# SCH__Atlas_2026-06-21.net
KiCad netlist of a schematic drawn in EasyEDA
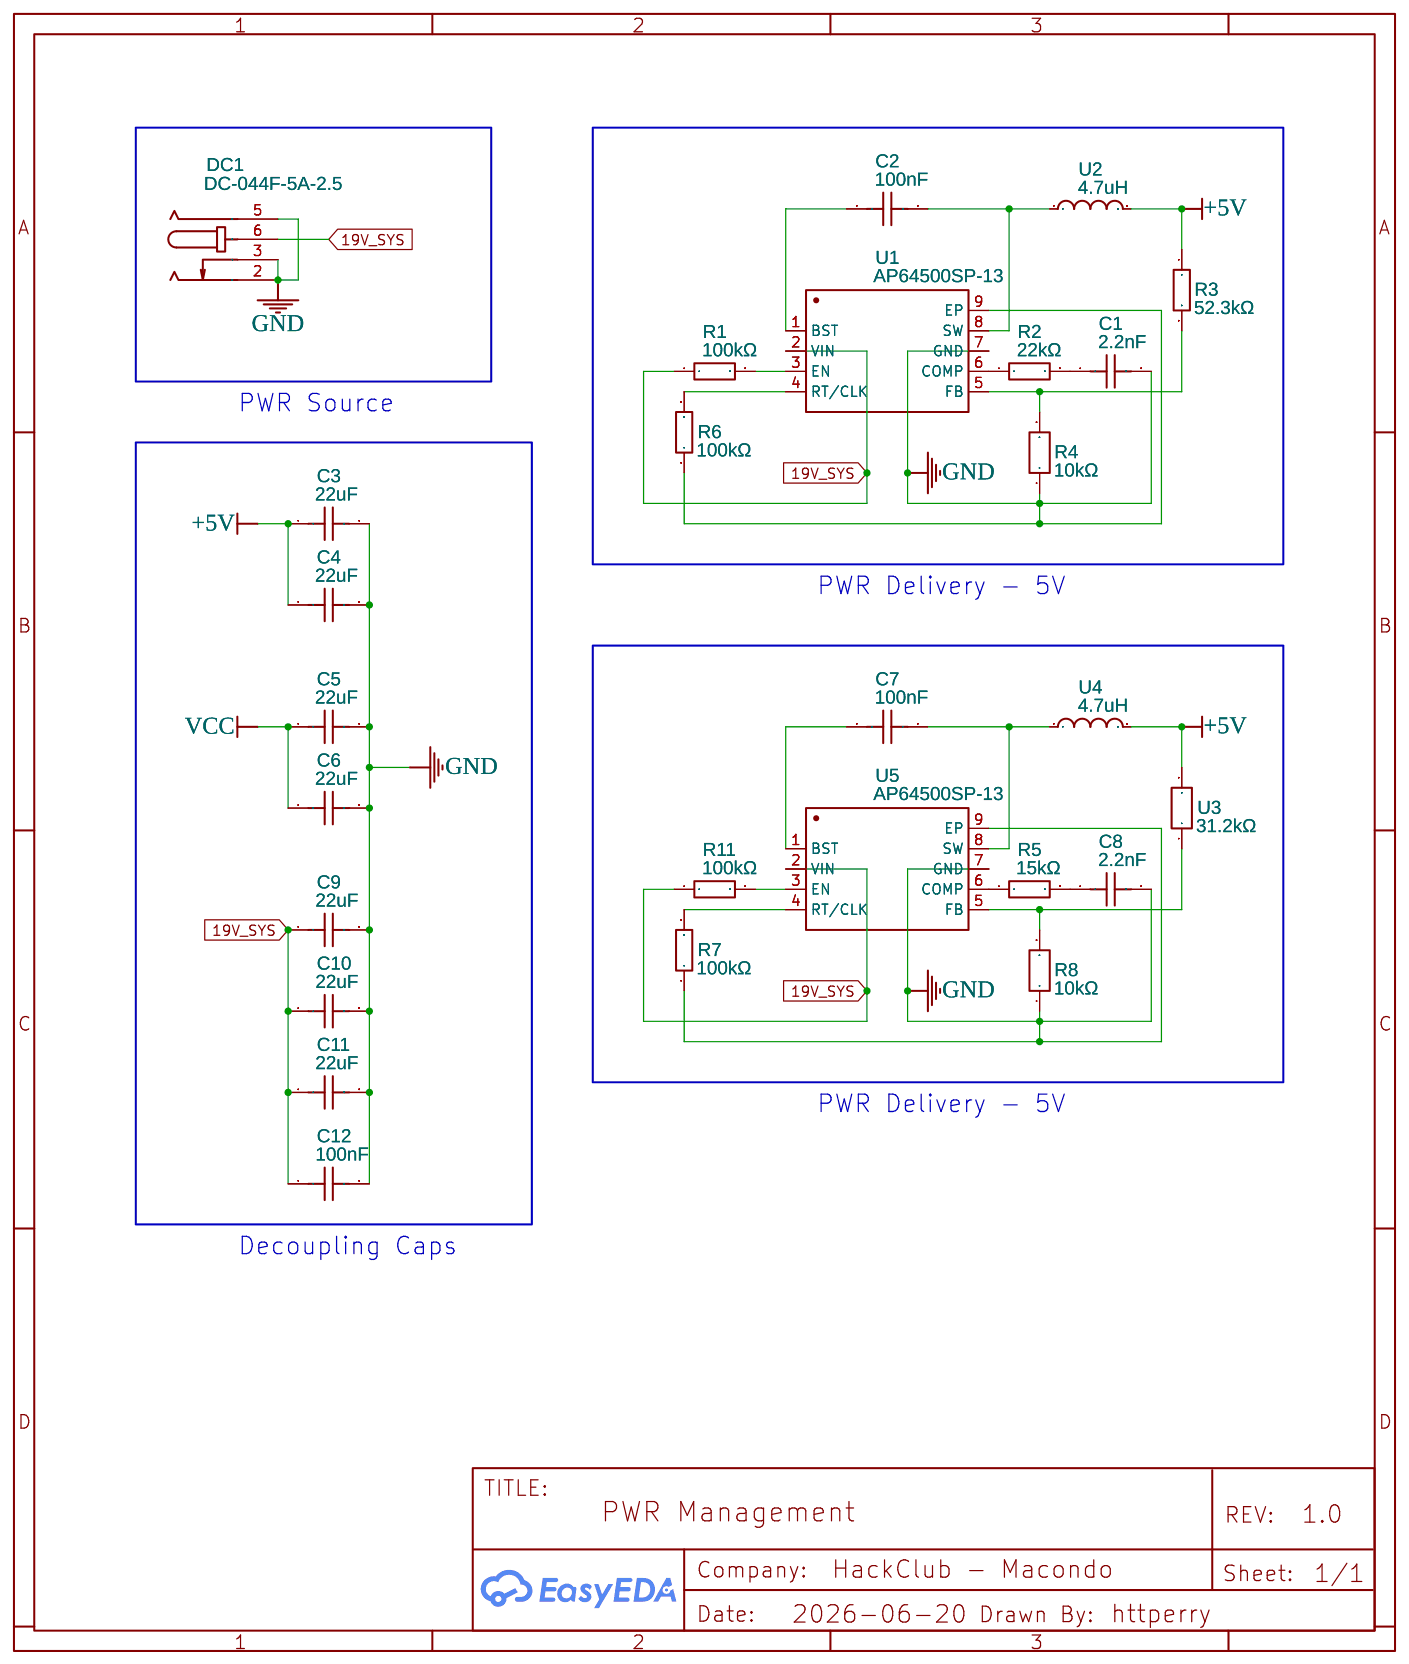
[diagram p0: PWR_Management]
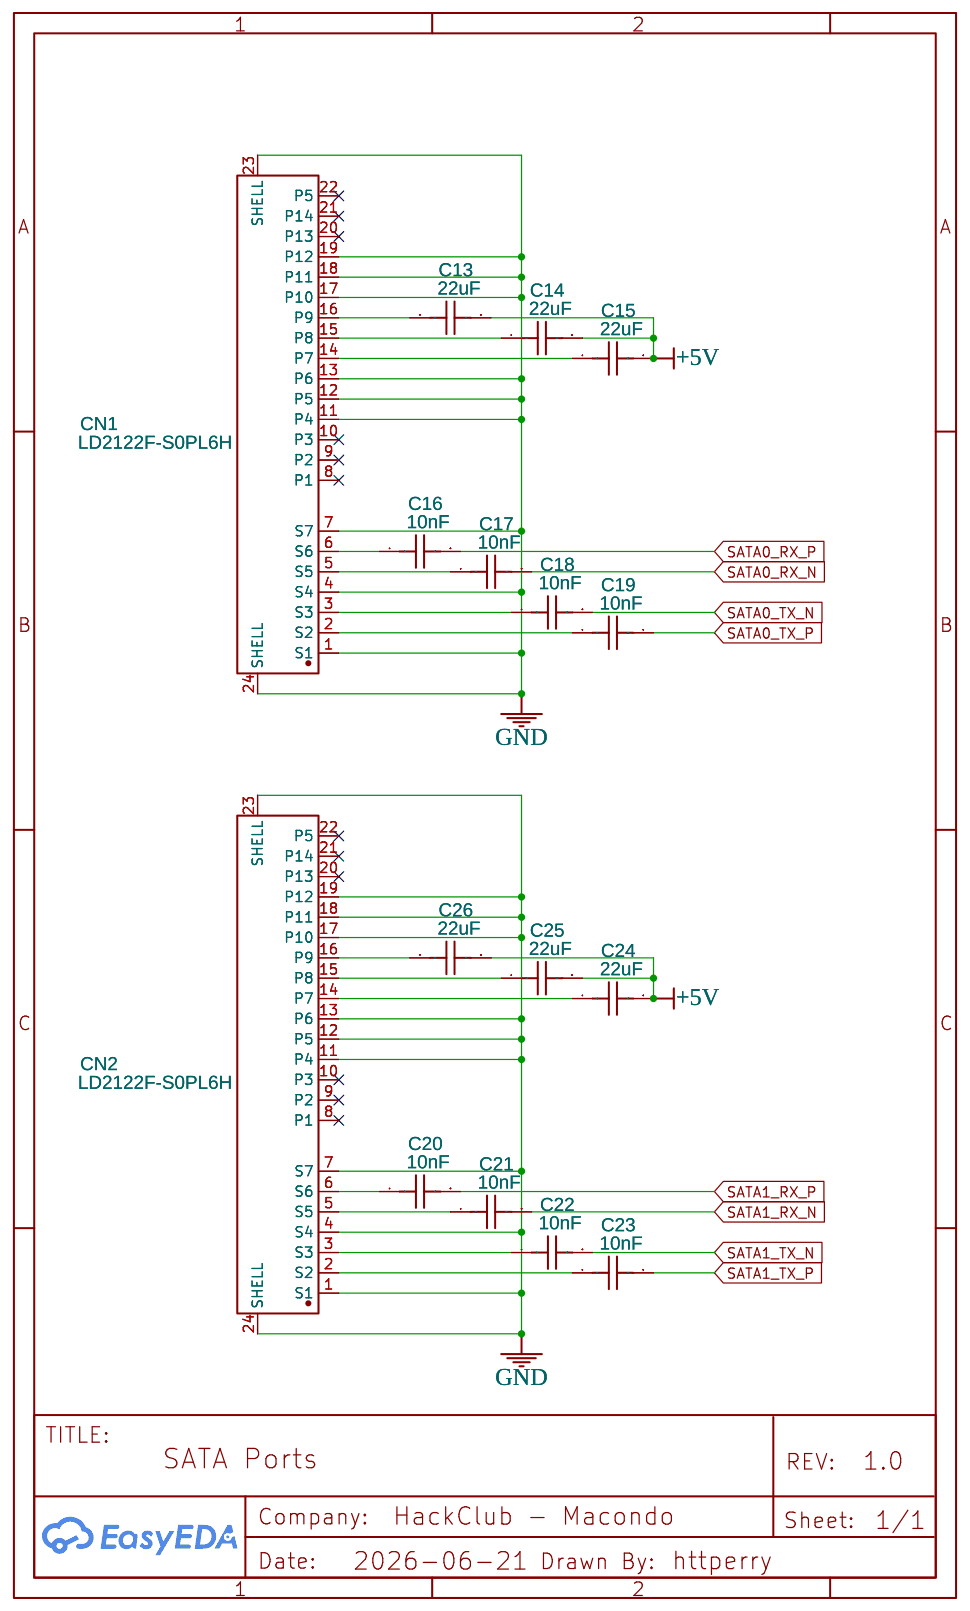
[diagram p1: SATA_Ports]
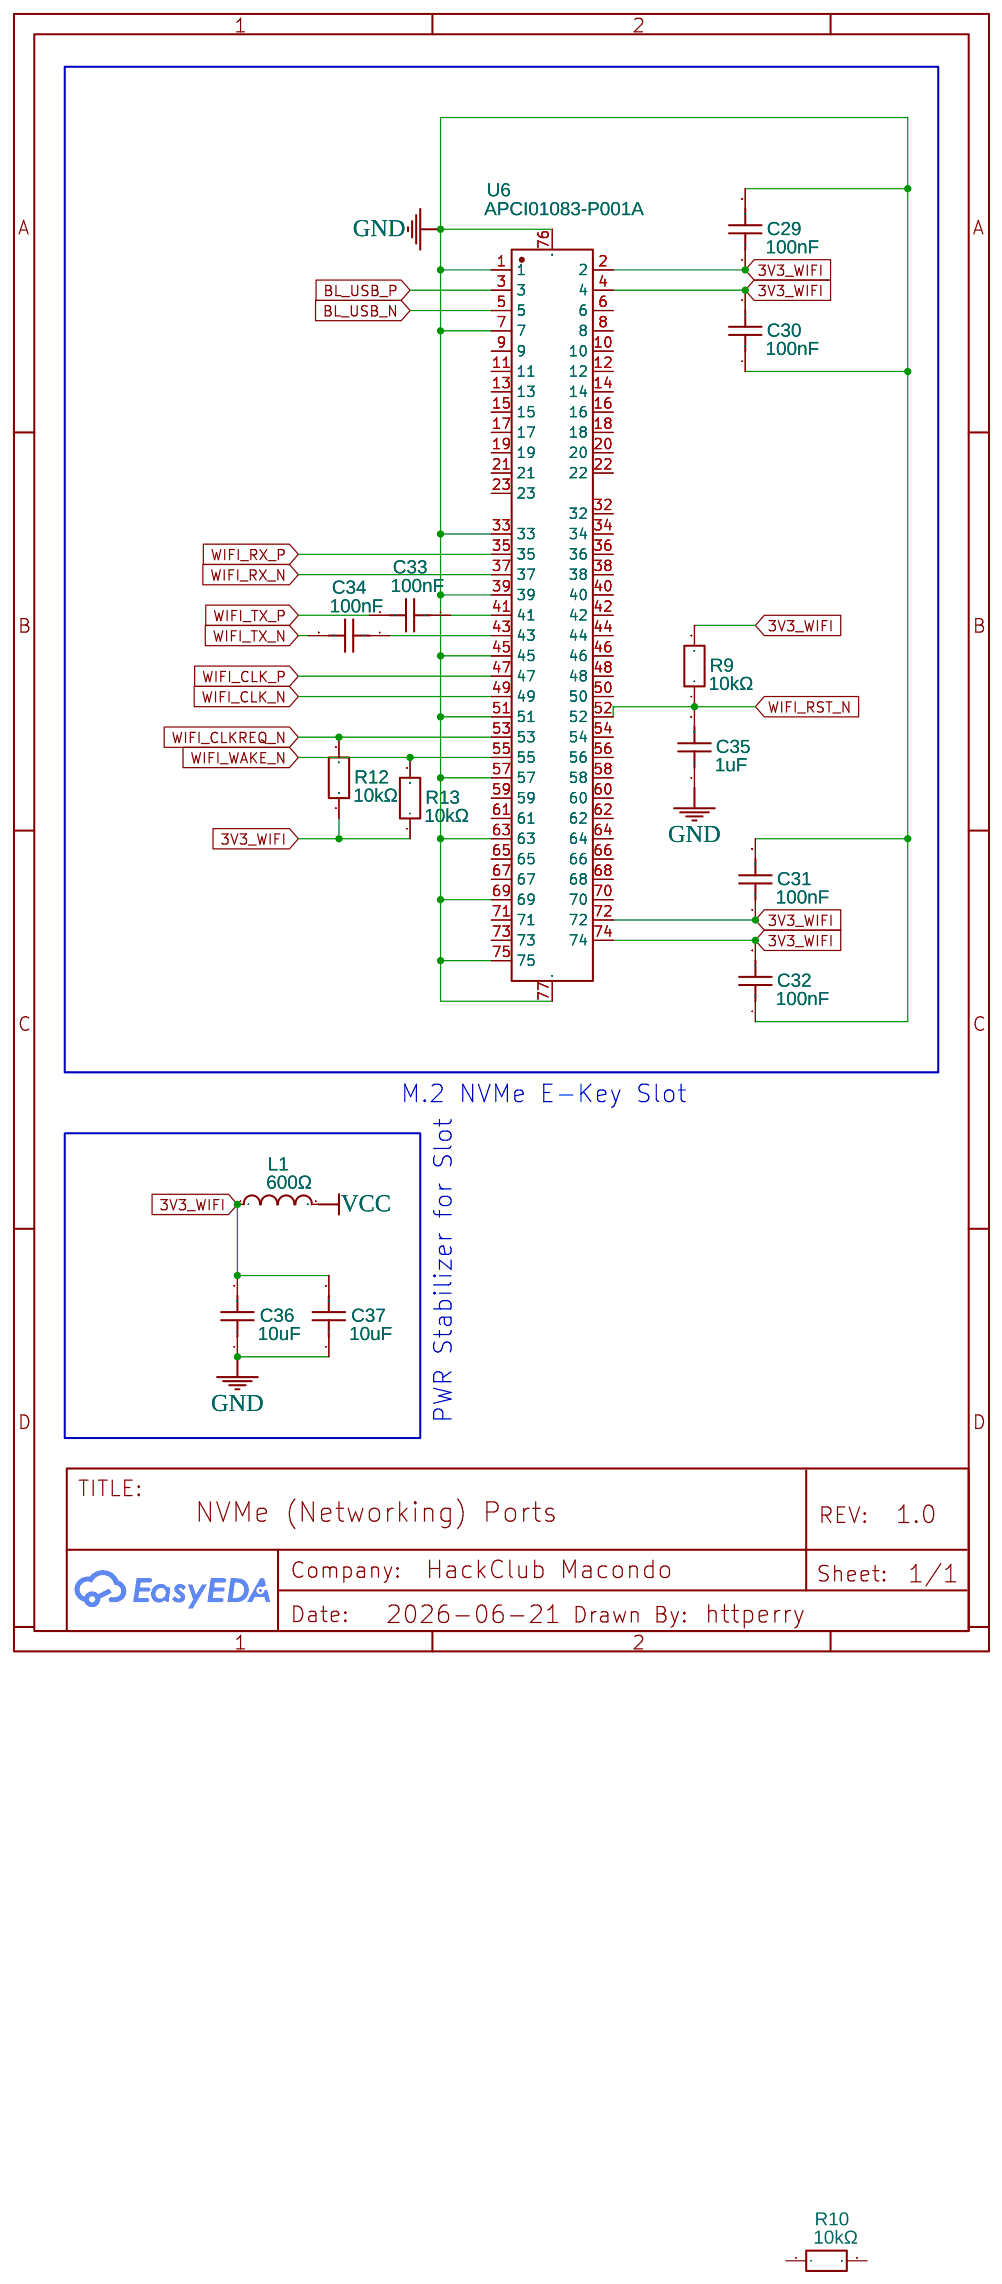
[diagram p2: NVMe_(Networking)_Ports]

(export (version "E")
  (design (tool "Eeschema 10.0.6"))
  (components
    (comp (ref "C1")
      (value "2.2nF")
      (fields
        (field (name "Manufacturer Part") "FCC0603B222K500CT")
        (field (name "Manufacturer") "FOJAN(富捷)")
      )
      (libsource (lib "") (part "FCC0603B222K500CT"))
    )
    (comp (ref "C2")
      (value "100nF")
      (fields
        (field (name "Manufacturer Part") "GRM188R71H104KA93D")
        (field (name "Manufacturer") "muRata(村田)")
      )
      (libsource (lib "") (part "GRM188R71H104KA93D"))
    )
    (comp (ref "C3")
      (value "22uF")
      (fields
        (field (name "Manufacturer Part") "HGC0603R5226M160NTHJ")
        (field (name "Manufacturer") "Chinocera(华瓷)")
      )
      (libsource (lib "") (part "HGC0603R5226M160NTHJ"))
    )
    (comp (ref "C4")
      (value "22uF")
      (fields
        (field (name "Manufacturer Part") "HGC0603R5226M160NTHJ")
        (field (name "Manufacturer") "Chinocera(华瓷)")
      )
      (libsource (lib "") (part "HGC0603R5226M160NTHJ"))
    )
    (comp (ref "C5")
      (value "22uF")
      (fields
        (field (name "Manufacturer Part") "HGC0603R5226M160NTHJ")
        (field (name "Manufacturer") "Chinocera(华瓷)")
      )
      (libsource (lib "") (part "HGC0603R5226M160NTHJ"))
    )
    (comp (ref "C6")
      (value "22uF")
      (fields
        (field (name "Manufacturer Part") "HGC0603R5226M160NTHJ")
        (field (name "Manufacturer") "Chinocera(华瓷)")
      )
      (libsource (lib "") (part "HGC0603R5226M160NTHJ"))
    )
    (comp (ref "C7")
      (value "100nF")
      (fields
        (field (name "Manufacturer Part") "GRM188R71H104KA93D")
        (field (name "Manufacturer") "muRata(村田)")
      )
      (libsource (lib "") (part "GRM188R71H104KA93D"))
    )
    (comp (ref "C8")
      (value "2.2nF")
      (fields
        (field (name "Manufacturer Part") "FCC0603B222K500CT")
        (field (name "Manufacturer") "FOJAN(富捷)")
      )
      (libsource (lib "") (part "FCC0603B222K500CT"))
    )
    (comp (ref "C9")
      (value "22uF")
      (fields
        (field (name "Manufacturer Part") "KCM55QR71H226KH13K")
        (field (name "Manufacturer") "muRata(村田)")
      )
      (libsource (lib "") (part "KCM55QR71H226KH13K"))
    )
    (comp (ref "C10")
      (value "22uF")
      (fields
        (field (name "Manufacturer Part") "KCM55QR71H226KH13K")
        (field (name "Manufacturer") "muRata(村田)")
      )
      (libsource (lib "") (part "KCM55QR71H226KH13K"))
    )
    (comp (ref "C11")
      (value "22uF")
      (fields
        (field (name "Manufacturer Part") "KCM55QR71H226KH13K")
        (field (name "Manufacturer") "muRata(村田)")
      )
      (libsource (lib "") (part "KCM55QR71H226KH13K"))
    )
    (comp (ref "C12")
      (value "100nF")
      (fields
        (field (name "Manufacturer Part") "GRM188R71H104KA93D")
        (field (name "Manufacturer") "muRata(村田)")
      )
      (libsource (lib "") (part "GRM188R71H104KA93D"))
    )
    (comp (ref "DC1")
      (value "DC-044F-5A-2.5")
      (fields (field (name "Manufacturer") "XKB Connection(中国星坤)"))
      (libsource (lib "") (part "DC-044F-5A-2.5"))
    )
    (comp (ref "R1")
      (value "100kΩ")
      (fields (field (name "Manufacturer Part") "RS-03K1003FT") (field (name "Manufacturer") "FH(风华)"))
      (libsource (lib "") (part "RS-03K1003FT_C115320_1"))
    )
    (comp (ref "R2")
      (value "22kΩ")
      (fields (field (name "Manufacturer Part") "RS-03K2202FT") (field (name "Manufacturer") "FH(风华)"))
      (libsource (lib "") (part "RS-03K2202FT"))
    )
    (comp (ref "R3")
      (value "52.3kΩ")
      (fields (field (name "Manufacturer Part") "RS-03K5232FT") (field (name "Manufacturer") "FH(风华)"))
      (libsource (lib "") (part "RS-03K5232FT"))
    )
    (comp (ref "R4")
      (value "10kΩ")
      (fields (field (name "Manufacturer Part") "AR03BTS1002") (field (name "Manufacturer") "Viking(光颉)"))
      (libsource (lib "") (part "AR03BTS1002"))
    )
    (comp (ref "R5")
      (value "15kΩ")
      (fields (field (name "Manufacturer Part") "CR0603FA1502G") (field (name "Manufacturer") "LIZ(丽智电子)"))
      (libsource (lib "") (part "CR0603FA1502G"))
    )
    (comp (ref "R6")
      (value "100kΩ")
      (fields (field (name "Manufacturer Part") "RS-03K1003FT") (field (name "Manufacturer") "FH(风华)"))
      (libsource (lib "") (part "RS-03K1003FT_C115320"))
    )
    (comp (ref "R7")
      (value "100kΩ")
      (fields (field (name "Manufacturer Part") "RS-03K1003FT") (field (name "Manufacturer") "FH(风华)"))
      (libsource (lib "") (part "RS-03K1003FT_C115320"))
    )
    (comp (ref "R8")
      (value "10kΩ")
      (fields (field (name "Manufacturer Part") "AR03BTS1002") (field (name "Manufacturer") "Viking(光颉)"))
      (libsource (lib "") (part "AR03BTS1002"))
    )
    (comp (ref "R11")
      (value "100kΩ")
      (fields (field (name "Manufacturer Part") "RS-03K1003FT") (field (name "Manufacturer") "FH(风华)"))
      (libsource (lib "") (part "RS-03K1003FT_C115320_1"))
    )
    (comp (ref "U1")
      (value "AP64500SP-13")
      (fields (field (name "Manufacturer") "DIODES(美台)"))
      (libsource (lib "") (part "AP64500SP-13"))
    )
    (comp (ref "U2")
      (value "4.7uH")
      (fields (field (name "Manufacturer Part") "APH0630T4R7M") (field (name "Manufacturer") "APV(爱普微)"))
      (libsource (lib "") (part "APH0630T4R7M"))
    )
    (comp (ref "U3")
      (value "31.2kΩ")
      (fields (field (name "Manufacturer Part") "RT0603DRE0731K2L") (field (name "Manufacturer") "YAGEO(国巨)"))
      (libsource (lib "") (part "RT0603DRE0731K2L"))
    )
    (comp (ref "U4")
      (value "4.7uH")
      (fields (field (name "Manufacturer Part") "APH0630T4R7M") (field (name "Manufacturer") "APV(爱普微)"))
      (libsource (lib "") (part "APH0630T4R7M"))
    )
    (comp (ref "U5")
      (value "AP64500SP-13")
      (fields (field (name "Manufacturer") "DIODES(美台)"))
      (libsource (lib "") (part "AP64500SP-13"))
    )
    (comp (ref "C13")
      (value "22uF")
      (fields
        (field (name "Manufacturer Part") "HGC0603R5226M160NTHJ")
        (field (name "Manufacturer") "Chinocera(华瓷)")
      )
      (libsource (lib "") (part "HGC0603R5226M160NTHJ"))
    )
    (comp (ref "C14")
      (value "22uF")
      (fields
        (field (name "Manufacturer Part") "HGC0603R5226M160NTHJ")
        (field (name "Manufacturer") "Chinocera(华瓷)")
      )
      (libsource (lib "") (part "HGC0603R5226M160NTHJ"))
    )
    (comp (ref "C15")
      (value "22uF")
      (fields
        (field (name "Manufacturer Part") "HGC0603R5226M160NTHJ")
        (field (name "Manufacturer") "Chinocera(华瓷)")
      )
      (libsource (lib "") (part "HGC0603R5226M160NTHJ"))
    )
    (comp (ref "C16")
      (value "10nF")
      (fields
        (field (name "Manufacturer Part") "FCC0402B103K500AT")
        (field (name "Manufacturer") "FOJAN(富捷)")
      )
      (libsource (lib "") (part "FCC0402B103K500AT"))
    )
    (comp (ref "C17")
      (value "10nF")
      (fields
        (field (name "Manufacturer Part") "FCC0402B103K500AT")
        (field (name "Manufacturer") "FOJAN(富捷)")
      )
      (libsource (lib "") (part "FCC0402B103K500AT"))
    )
    (comp (ref "C18")
      (value "10nF")
      (fields
        (field (name "Manufacturer Part") "FCC0402B103K500AT")
        (field (name "Manufacturer") "FOJAN(富捷)")
      )
      (libsource (lib "") (part "FCC0402B103K500AT"))
    )
    (comp (ref "C19")
      (value "10nF")
      (fields
        (field (name "Manufacturer Part") "FCC0402B103K500AT")
        (field (name "Manufacturer") "FOJAN(富捷)")
      )
      (libsource (lib "") (part "FCC0402B103K500AT"))
    )
    (comp (ref "C20")
      (value "10nF")
      (fields
        (field (name "Manufacturer Part") "FCC0402B103K500AT")
        (field (name "Manufacturer") "FOJAN(富捷)")
      )
      (libsource (lib "") (part "FCC0402B103K500AT"))
    )
    (comp (ref "C21")
      (value "10nF")
      (fields
        (field (name "Manufacturer Part") "FCC0402B103K500AT")
        (field (name "Manufacturer") "FOJAN(富捷)")
      )
      (libsource (lib "") (part "FCC0402B103K500AT"))
    )
    (comp (ref "C22")
      (value "10nF")
      (fields
        (field (name "Manufacturer Part") "FCC0402B103K500AT")
        (field (name "Manufacturer") "FOJAN(富捷)")
      )
      (libsource (lib "") (part "FCC0402B103K500AT"))
    )
    (comp (ref "C23")
      (value "10nF")
      (fields
        (field (name "Manufacturer Part") "FCC0402B103K500AT")
        (field (name "Manufacturer") "FOJAN(富捷)")
      )
      (libsource (lib "") (part "FCC0402B103K500AT"))
    )
    (comp (ref "C24")
      (value "22uF")
      (fields
        (field (name "Manufacturer Part") "HGC0603R5226M160NTHJ")
        (field (name "Manufacturer") "Chinocera(华瓷)")
      )
      (libsource (lib "") (part "HGC0603R5226M160NTHJ"))
    )
    (comp (ref "C25")
      (value "22uF")
      (fields
        (field (name "Manufacturer Part") "HGC0603R5226M160NTHJ")
        (field (name "Manufacturer") "Chinocera(华瓷)")
      )
      (libsource (lib "") (part "HGC0603R5226M160NTHJ"))
    )
    (comp (ref "C26")
      (value "22uF")
      (fields
        (field (name "Manufacturer Part") "HGC0603R5226M160NTHJ")
        (field (name "Manufacturer") "Chinocera(华瓷)")
      )
      (libsource (lib "") (part "HGC0603R5226M160NTHJ"))
    )
    (comp (ref "CN1")
      (value "LD2122F-S0PL6H")
      (fields (field (name "Manufacturer") "FOXCONN(富士康)"))
      (libsource (lib "") (part "LD2122F-S0PL6H"))
    )
    (comp (ref "CN2")
      (value "LD2122F-S0PL6H")
      (fields (field (name "Manufacturer") "FOXCONN(富士康)"))
      (libsource (lib "") (part "LD2122F-S0PL6H"))
    )
    (comp (ref "C29")
      (value "100nF")
      (fields
        (field (name "Manufacturer Part") "CC0402KRX5R6BB104")
        (field (name "Manufacturer") "YAGEO(国巨)")
      )
      (libsource (lib "") (part "CC0402KRX5R6BB104"))
    )
    (comp (ref "C30")
      (value "100nF")
      (fields
        (field (name "Manufacturer Part") "CC0402KRX5R6BB104")
        (field (name "Manufacturer") "YAGEO(国巨)")
      )
      (libsource (lib "") (part "CC0402KRX5R6BB104"))
    )
    (comp (ref "C31")
      (value "100nF")
      (fields
        (field (name "Manufacturer Part") "CC0402KRX5R6BB104")
        (field (name "Manufacturer") "YAGEO(国巨)")
      )
      (libsource (lib "") (part "CC0402KRX5R6BB104"))
    )
    (comp (ref "C32")
      (value "100nF")
      (fields
        (field (name "Manufacturer Part") "CC0402KRX5R6BB104")
        (field (name "Manufacturer") "YAGEO(国巨)")
      )
      (libsource (lib "") (part "CC0402KRX5R6BB104"))
    )
    (comp (ref "C33")
      (value "100nF")
      (fields
        (field (name "Manufacturer Part") "CC0402KRX5R6BB104")
        (field (name "Manufacturer") "YAGEO(国巨)")
      )
      (libsource (lib "") (part "CC0402KRX5R6BB104_1"))
    )
    (comp (ref "C34")
      (value "100nF")
      (fields
        (field (name "Manufacturer Part") "CC0402KRX5R6BB104")
        (field (name "Manufacturer") "YAGEO(国巨)")
      )
      (libsource (lib "") (part "CC0402KRX5R6BB104_1"))
    )
    (comp (ref "C35")
      (value "1uF")
      (fields
        (field (name "Manufacturer Part") "TCC0402X5R105K160AT")
        (field (name "Manufacturer") "CCTC(三环)")
      )
      (libsource (lib "") (part "TCC0402X5R105K160AT"))
    )
    (comp (ref "C36")
      (value "10uF")
      (fields
        (field (name "Manufacturer Part") "CGA0805X5R106K500MT")
        (field (name "Manufacturer") "HRE(芯声)")
      )
      (libsource (lib "") (part "CGA0805X5R106K500MT"))
    )
    (comp (ref "C37")
      (value "10uF")
      (fields
        (field (name "Manufacturer Part") "CGA0805X5R106K500MT")
        (field (name "Manufacturer") "HRE(芯声)")
      )
      (libsource (lib "") (part "CGA0805X5R106K500MT"))
    )
    (comp (ref "L1")
      (value "600Ω")
      (fields (field (name "Manufacturer Part") "MPZ2012S601AT000") (field (name "Manufacturer") "TDK"))
      (libsource (lib "") (part "MPZ2012S601AT000"))
    )
    (comp (ref "R9")
      (value "10kΩ")
      (fields (field (name "Manufacturer Part") "FRC0402F1002TS") (field (name "Manufacturer") "FOJAN(富捷)"))
      (libsource (lib "") (part "FRC0402F1002TS_1"))
    )
    (comp (ref "R10")
      (value "10kΩ")
      (fields (field (name "Manufacturer Part") "FRC0402F1002TS") (field (name "Manufacturer") "FOJAN(富捷)"))
      (libsource (lib "") (part "FRC0402F1002TS"))
    )
    (comp (ref "R12")
      (value "10kΩ")
      (fields (field (name "Manufacturer Part") "FRC0402F1002TS") (field (name "Manufacturer") "FOJAN(富捷)"))
      (libsource (lib "") (part "FRC0402F1002TS_1"))
    )
    (comp (ref "R13")
      (value "10kΩ")
      (fields (field (name "Manufacturer Part") "FRC0402F1002TS") (field (name "Manufacturer") "FOJAN(富捷)"))
      (libsource (lib "") (part "FRC0402F1002TS_1"))
    )
    (comp (ref "U6")
      (value "APCI01083-P001A")
      (fields (field (name "Manufacturer") "LX(连欣科技)"))
      (libsource (lib "") (part "APCI01083-P001A"))
    )
  )
  (nets
    (net (code "1") (name "+5V") (class "Default")
      (node (ref "C13") (pin "2") (pinfunction "2_2") (pintype "unspecified"))
      (node (ref "C14") (pin "2") (pinfunction "2_2") (pintype "unspecified"))
      (node (ref "C15") (pin "2") (pinfunction "2_2") (pintype "unspecified"))
      (node (ref "C24") (pin "2") (pinfunction "2_2") (pintype "unspecified"))
      (node (ref "C25") (pin "2") (pinfunction "2_2") (pintype "unspecified"))
      (node (ref "C26") (pin "2") (pinfunction "2_2") (pintype "unspecified"))
      (node (ref "C3") (pin "1") (pinfunction "1_1") (pintype "unspecified"))
      (node (ref "C4") (pin "1") (pinfunction "1_1") (pintype "unspecified"))
      (node (ref "R3") (pin "1") (pinfunction "1_1") (pintype "unspecified"))
      (node (ref "U2") (pin "2") (pinfunction "2_2") (pintype "unspecified"))
      (node (ref "U3") (pin "2") (pinfunction "2_2") (pintype "unspecified"))
      (node (ref "U4") (pin "2") (pinfunction "2_2") (pintype "unspecified"))
    )
    (net (code "2") (name "3V3_WIFI") (class "Default")
      (node (ref "C29") (pin "1") (pinfunction "1_1") (pintype "unspecified"))
      (node (ref "C30") (pin "2") (pinfunction "2_2") (pintype "unspecified"))
      (node (ref "C31") (pin "1") (pinfunction "1_1") (pintype "unspecified"))
      (node (ref "C32") (pin "2") (pinfunction "2_2") (pintype "unspecified"))
      (node (ref "C36") (pin "2") (pinfunction "2_2") (pintype "unspecified"))
      (node (ref "C37") (pin "2") (pinfunction "2_2") (pintype "unspecified"))
      (node (ref "L1") (pin "1") (pinfunction "1_1") (pintype "unspecified"))
      (node (ref "R12") (pin "1") (pinfunction "1_1") (pintype "unspecified"))
      (node (ref "R13") (pin "1") (pinfunction "1_1") (pintype "unspecified"))
      (node (ref "R9") (pin "2") (pinfunction "2_2") (pintype "unspecified"))
      (node (ref "U6") (pin "2") (pinfunction "2_2") (pintype "unspecified"))
      (node (ref "U6") (pin "4") (pinfunction "4_4") (pintype "unspecified"))
      (node (ref "U6") (pin "72") (pinfunction "72_72") (pintype "unspecified"))
      (node (ref "U6") (pin "74") (pinfunction "74_74") (pintype "unspecified"))
    )
    (net (code "3") (name "19V_SYS") (class "Default")
      (node (ref "C10") (pin "1") (pinfunction "1_1") (pintype "unspecified"))
      (node (ref "C11") (pin "1") (pinfunction "1_1") (pintype "unspecified"))
      (node (ref "C12") (pin "1") (pinfunction "1_1") (pintype "unspecified"))
      (node (ref "C9") (pin "1") (pinfunction "1_1") (pintype "unspecified"))
      (node (ref "DC1") (pin "6") (pinfunction "6_6") (pintype "unspecified"))
      (node (ref "R1") (pin "1") (pinfunction "1_1") (pintype "unspecified"))
      (node (ref "R11") (pin "1") (pinfunction "1_1") (pintype "unspecified"))
      (node (ref "U1") (pin "2") (pinfunction "VIN_2") (pintype "unspecified"))
      (node (ref "U5") (pin "2") (pinfunction "VIN_2") (pintype "unspecified"))
    )
    (net (code "4") (name "BL_USB_N") (class "Default")
      (node (ref "U6") (pin "5") (pinfunction "5_5") (pintype "unspecified"))
    )
    (net (code "5") (name "BL_USB_P") (class "Default")
      (node (ref "U6") (pin "3") (pinfunction "3_3") (pintype "unspecified"))
    )
    (net (code "6") (name "GND") (class "Default")
      (node (ref "C1") (pin "2") (pinfunction "2_2") (pintype "unspecified"))
      (node (ref "C10") (pin "2") (pinfunction "2_2") (pintype "unspecified"))
      (node (ref "C11") (pin "2") (pinfunction "2_2") (pintype "unspecified"))
      (node (ref "C12") (pin "2") (pinfunction "2_2") (pintype "unspecified"))
      (node (ref "C29") (pin "2") (pinfunction "2_2") (pintype "unspecified"))
      (node (ref "C3") (pin "2") (pinfunction "2_2") (pintype "unspecified"))
      (node (ref "C30") (pin "1") (pinfunction "1_1") (pintype "unspecified"))
      (node (ref "C31") (pin "2") (pinfunction "2_2") (pintype "unspecified"))
      (node (ref "C32") (pin "1") (pinfunction "1_1") (pintype "unspecified"))
      (node (ref "C35") (pin "1") (pinfunction "1_1") (pintype "unspecified"))
      (node (ref "C36") (pin "1") (pinfunction "1_1") (pintype "unspecified"))
      (node (ref "C37") (pin "1") (pinfunction "1_1") (pintype "unspecified"))
      (node (ref "C4") (pin "2") (pinfunction "2_2") (pintype "unspecified"))
      (node (ref "C5") (pin "2") (pinfunction "2_2") (pintype "unspecified"))
      (node (ref "C6") (pin "2") (pinfunction "2_2") (pintype "unspecified"))
      (node (ref "C8") (pin "2") (pinfunction "2_2") (pintype "unspecified"))
      (node (ref "C9") (pin "2") (pinfunction "2_2") (pintype "unspecified"))
      (node (ref "CN1") (pin "1") (pinfunction "S1_1") (pintype "unspecified"))
      (node (ref "CN1") (pin "11") (pinfunction "P4_11") (pintype "unspecified"))
      (node (ref "CN1") (pin "12") (pinfunction "P5_12") (pintype "unspecified"))
      (node (ref "CN1") (pin "13") (pinfunction "P6_13") (pintype "unspecified"))
      (node (ref "CN1") (pin "17") (pinfunction "P10_17") (pintype "unspecified"))
      (node (ref "CN1") (pin "18") (pinfunction "P11_18") (pintype "unspecified"))
      (node (ref "CN1") (pin "19") (pinfunction "P12_19") (pintype "unspecified"))
      (node (ref "CN1") (pin "23") (pinfunction "SHELL_23") (pintype "unspecified"))
      (node (ref "CN1") (pin "24") (pinfunction "SHELL_24") (pintype "unspecified"))
      (node (ref "CN1") (pin "4") (pinfunction "S4_4") (pintype "unspecified"))
      (node (ref "CN1") (pin "7") (pinfunction "S7_7") (pintype "unspecified"))
      (node (ref "CN2") (pin "1") (pinfunction "S1_1") (pintype "unspecified"))
      (node (ref "CN2") (pin "11") (pinfunction "P4_11") (pintype "unspecified"))
      (node (ref "CN2") (pin "12") (pinfunction "P5_12") (pintype "unspecified"))
      (node (ref "CN2") (pin "13") (pinfunction "P6_13") (pintype "unspecified"))
      (node (ref "CN2") (pin "17") (pinfunction "P10_17") (pintype "unspecified"))
      (node (ref "CN2") (pin "18") (pinfunction "P11_18") (pintype "unspecified"))
      (node (ref "CN2") (pin "19") (pinfunction "P12_19") (pintype "unspecified"))
      (node (ref "CN2") (pin "23") (pinfunction "SHELL_23") (pintype "unspecified"))
      (node (ref "CN2") (pin "24") (pinfunction "SHELL_24") (pintype "unspecified"))
      (node (ref "CN2") (pin "4") (pinfunction "S4_4") (pintype "unspecified"))
      (node (ref "CN2") (pin "7") (pinfunction "S7_7") (pintype "unspecified"))
      (node (ref "DC1") (pin "2") (pinfunction "2_2") (pintype "unspecified"))
      (node (ref "DC1") (pin "3") (pinfunction "3_3") (pintype "unspecified"))
      (node (ref "DC1") (pin "5") (pinfunction "5_5") (pintype "unspecified"))
      (node (ref "R4") (pin "1") (pinfunction "1_1") (pintype "unspecified"))
      (node (ref "R6") (pin "1") (pinfunction "1_1") (pintype "unspecified"))
      (node (ref "R7") (pin "1") (pinfunction "1_1") (pintype "unspecified"))
      (node (ref "R8") (pin "1") (pinfunction "1_1") (pintype "unspecified"))
      (node (ref "U1") (pin "7") (pinfunction "GND_7") (pintype "unspecified"))
      (node (ref "U1") (pin "9") (pinfunction "EP_9") (pintype "unspecified"))
      (node (ref "U5") (pin "7") (pinfunction "GND_7") (pintype "unspecified"))
      (node (ref "U5") (pin "9") (pinfunction "EP_9") (pintype "unspecified"))
      (node (ref "U6") (pin "1") (pinfunction "1_1") (pintype "unspecified"))
      (node (ref "U6") (pin "33") (pinfunction "33_33") (pintype "unspecified"))
      (node (ref "U6") (pin "39") (pinfunction "39_39") (pintype "unspecified"))
      (node (ref "U6") (pin "45") (pinfunction "45_45") (pintype "unspecified"))
      (node (ref "U6") (pin "51") (pinfunction "51_51") (pintype "unspecified"))
      (node (ref "U6") (pin "57") (pinfunction "57_57") (pintype "unspecified"))
      (node (ref "U6") (pin "63") (pinfunction "63_63") (pintype "unspecified"))
      (node (ref "U6") (pin "69") (pinfunction "69_69") (pintype "unspecified"))
      (node (ref "U6") (pin "7") (pinfunction "7_7") (pintype "unspecified"))
      (node (ref "U6") (pin "75") (pinfunction "75_75") (pintype "unspecified"))
      (node (ref "U6") (pin "76") (pinfunction "76_76") (pintype "unspecified"))
      (node (ref "U6") (pin "77") (pinfunction "77_77") (pintype "unspecified"))
    )
    (net (code "7") (name "Net-(C1-Pad1)") (class "Default")
      (node (ref "C1") (pin "1") (pinfunction "1_1") (pintype "unspecified"))
      (node (ref "R2") (pin "2") (pinfunction "2_2") (pintype "unspecified"))
    )
    (net (code "8") (name "Net-(C8-Pad1)") (class "Default")
      (node (ref "C8") (pin "1") (pinfunction "1_1") (pintype "unspecified"))
      (node (ref "R5") (pin "2") (pinfunction "2_2") (pintype "input"))
    )
    (net (code "9") (name "Net-(C33-Pad1)") (class "Default")
      (node (ref "C33") (pin "1") (pinfunction "1_1") (pintype "unspecified"))
      (node (ref "U6") (pin "41") (pinfunction "41_41") (pintype "unspecified"))
    )
    (net (code "10") (name "Net-(C34-Pad1)") (class "Default")
      (node (ref "C34") (pin "1") (pinfunction "1_1") (pintype "unspecified"))
      (node (ref "U6") (pin "43") (pinfunction "43_43") (pintype "unspecified"))
    )
    (net (code "11") (name "Net-(CN1-P7)") (class "Default")
      (node (ref "C15") (pin "1") (pinfunction "1_1") (pintype "unspecified"))
      (node (ref "CN1") (pin "14") (pinfunction "P7_14") (pintype "unspecified"))
    )
    (net (code "12") (name "Net-(CN1-P8)") (class "Default")
      (node (ref "C14") (pin "1") (pinfunction "1_1") (pintype "unspecified"))
      (node (ref "CN1") (pin "15") (pinfunction "P8_15") (pintype "unspecified"))
    )
    (net (code "13") (name "Net-(CN1-P9)") (class "Default")
      (node (ref "C13") (pin "1") (pinfunction "1_1") (pintype "unspecified"))
      (node (ref "CN1") (pin "16") (pinfunction "P9_16") (pintype "unspecified"))
    )
    (net (code "14") (name "Net-(CN1-S2)") (class "Default")
      (node (ref "C19") (pin "1") (pinfunction "1_1") (pintype "unspecified"))
      (node (ref "CN1") (pin "2") (pinfunction "S2_2") (pintype "unspecified"))
    )
    (net (code "15") (name "Net-(CN1-S3)") (class "Default")
      (node (ref "C18") (pin "1") (pinfunction "1_1") (pintype "unspecified"))
      (node (ref "CN1") (pin "3") (pinfunction "S3_3") (pintype "unspecified"))
    )
    (net (code "16") (name "Net-(CN1-S5)") (class "Default")
      (node (ref "C17") (pin "1") (pinfunction "1_1") (pintype "unspecified"))
      (node (ref "CN1") (pin "5") (pinfunction "S5_5") (pintype "unspecified"))
    )
    (net (code "17") (name "Net-(CN1-S6)") (class "Default")
      (node (ref "C16") (pin "1") (pinfunction "1_1") (pintype "unspecified"))
      (node (ref "CN1") (pin "6") (pinfunction "S6_6") (pintype "unspecified"))
    )
    (net (code "18") (name "Net-(CN2-P7)") (class "Default")
      (node (ref "C24") (pin "1") (pinfunction "1_1") (pintype "unspecified"))
      (node (ref "CN2") (pin "14") (pinfunction "P7_14") (pintype "unspecified"))
    )
    (net (code "19") (name "Net-(CN2-P8)") (class "Default")
      (node (ref "C25") (pin "1") (pinfunction "1_1") (pintype "unspecified"))
      (node (ref "CN2") (pin "15") (pinfunction "P8_15") (pintype "unspecified"))
    )
    (net (code "20") (name "Net-(CN2-P9)") (class "Default")
      (node (ref "C26") (pin "1") (pinfunction "1_1") (pintype "unspecified"))
      (node (ref "CN2") (pin "16") (pinfunction "P9_16") (pintype "unspecified"))
    )
    (net (code "21") (name "Net-(CN2-S2)") (class "Default")
      (node (ref "C23") (pin "1") (pinfunction "1_1") (pintype "unspecified"))
      (node (ref "CN2") (pin "2") (pinfunction "S2_2") (pintype "unspecified"))
    )
    (net (code "22") (name "Net-(CN2-S3)") (class "Default")
      (node (ref "C22") (pin "1") (pinfunction "1_1") (pintype "unspecified"))
      (node (ref "CN2") (pin "3") (pinfunction "S3_3") (pintype "unspecified"))
    )
    (net (code "23") (name "Net-(CN2-S5)") (class "Default")
      (node (ref "C21") (pin "1") (pinfunction "1_1") (pintype "unspecified"))
      (node (ref "CN2") (pin "5") (pinfunction "S5_5") (pintype "unspecified"))
    )
    (net (code "24") (name "Net-(CN2-S6)") (class "Default")
      (node (ref "C20") (pin "1") (pinfunction "1_1") (pintype "unspecified"))
      (node (ref "CN2") (pin "6") (pinfunction "S6_6") (pintype "unspecified"))
    )
    (net (code "25") (name "Net-(U1-BST)") (class "Default")
      (node (ref "C2") (pin "1") (pinfunction "1_1") (pintype "unspecified"))
      (node (ref "U1") (pin "1") (pinfunction "BST_1") (pintype "unspecified"))
    )
    (net (code "26") (name "Net-(U1-COMP)") (class "Default")
      (node (ref "R2") (pin "1") (pinfunction "1_1") (pintype "unspecified"))
      (node (ref "U1") (pin "6") (pinfunction "COMP_6") (pintype "unspecified"))
    )
    (net (code "27") (name "Net-(U1-EN)") (class "Default")
      (node (ref "R1") (pin "2") (pinfunction "2_2") (pintype "unspecified"))
      (node (ref "U1") (pin "3") (pinfunction "EN_3") (pintype "unspecified"))
    )
    (net (code "28") (name "Net-(U1-FB)") (class "Default")
      (node (ref "R3") (pin "2") (pinfunction "2_2") (pintype "unspecified"))
      (node (ref "R4") (pin "2") (pinfunction "2_2") (pintype "unspecified"))
      (node (ref "U1") (pin "5") (pinfunction "FB_5") (pintype "unspecified"))
    )
    (net (code "29") (name "Net-(U1-RT{slash}CLK)") (class "Default")
      (node (ref "R6") (pin "2") (pinfunction "2_2") (pintype "unspecified"))
      (node (ref "U1") (pin "4") (pinfunction "RT/CLK_4") (pintype "unspecified"))
    )
    (net (code "30") (name "Net-(U1-SW)") (class "Default")
      (node (ref "C2") (pin "2") (pinfunction "2_2") (pintype "unspecified"))
      (node (ref "U1") (pin "8") (pinfunction "SW_8") (pintype "unspecified"))
      (node (ref "U2") (pin "1") (pinfunction "1_1") (pintype "unspecified"))
    )
    (net (code "31") (name "Net-(U5-BST)") (class "Default")
      (node (ref "C7") (pin "1") (pinfunction "1_1") (pintype "unspecified"))
      (node (ref "U5") (pin "1") (pinfunction "BST_1") (pintype "unspecified"))
    )
    (net (code "32") (name "Net-(U5-COMP)") (class "Default")
      (node (ref "R5") (pin "1") (pinfunction "1_1") (pintype "input"))
      (node (ref "U5") (pin "6") (pinfunction "COMP_6") (pintype "unspecified"))
    )
    (net (code "33") (name "Net-(U5-EN)") (class "Default")
      (node (ref "R11") (pin "2") (pinfunction "2_2") (pintype "unspecified"))
      (node (ref "U5") (pin "3") (pinfunction "EN_3") (pintype "unspecified"))
    )
    (net (code "34") (name "Net-(U5-FB)") (class "Default")
      (node (ref "R8") (pin "2") (pinfunction "2_2") (pintype "unspecified"))
      (node (ref "U3") (pin "1") (pinfunction "1_1") (pintype "unspecified"))
      (node (ref "U5") (pin "5") (pinfunction "FB_5") (pintype "unspecified"))
    )
    (net (code "35") (name "Net-(U5-RT{slash}CLK)") (class "Default")
      (node (ref "R7") (pin "2") (pinfunction "2_2") (pintype "unspecified"))
      (node (ref "U5") (pin "4") (pinfunction "RT/CLK_4") (pintype "unspecified"))
    )
    (net (code "36") (name "Net-(U5-SW)") (class "Default")
      (node (ref "C7") (pin "2") (pinfunction "2_2") (pintype "unspecified"))
      (node (ref "U4") (pin "1") (pinfunction "1_1") (pintype "unspecified"))
      (node (ref "U5") (pin "8") (pinfunction "SW_8") (pintype "unspecified"))
    )
    (net (code "37") (name "SATA0_RX_N") (class "Default")
      (node (ref "C17") (pin "2") (pinfunction "2_2") (pintype "unspecified"))
    )
    (net (code "38") (name "SATA0_RX_P") (class "Default")
      (node (ref "C16") (pin "2") (pinfunction "2_2") (pintype "unspecified"))
    )
    (net (code "39") (name "SATA0_TX_N") (class "Default")
      (node (ref "C18") (pin "2") (pinfunction "2_2") (pintype "unspecified"))
    )
    (net (code "40") (name "SATA0_TX_P") (class "Default")
      (node (ref "C19") (pin "2") (pinfunction "2_2") (pintype "unspecified"))
    )
    (net (code "41") (name "SATA1_RX_N") (class "Default")
      (node (ref "C21") (pin "2") (pinfunction "2_2") (pintype "unspecified"))
    )
    (net (code "42") (name "SATA1_RX_P") (class "Default")
      (node (ref "C20") (pin "2") (pinfunction "2_2") (pintype "unspecified"))
    )
    (net (code "43") (name "SATA1_TX_N") (class "Default")
      (node (ref "C22") (pin "2") (pinfunction "2_2") (pintype "unspecified"))
    )
    (net (code "44") (name "SATA1_TX_P") (class "Default")
      (node (ref "C23") (pin "2") (pinfunction "2_2") (pintype "unspecified"))
    )
    (net (code "45") (name "VCC") (class "Default")
      (node (ref "C5") (pin "1") (pinfunction "1_1") (pintype "unspecified"))
      (node (ref "C6") (pin "1") (pinfunction "1_1") (pintype "unspecified"))
      (node (ref "L1") (pin "2") (pinfunction "2_2") (pintype "unspecified"))
    )
    (net (code "46") (name "WIFI_CLKREQ_N") (class "Default")
      (node (ref "R12") (pin "2") (pinfunction "2_2") (pintype "unspecified"))
      (node (ref "U6") (pin "53") (pinfunction "53_53") (pintype "unspecified"))
    )
    (net (code "47") (name "WIFI_CLK_N") (class "Default")
      (node (ref "U6") (pin "49") (pinfunction "49_49") (pintype "unspecified"))
    )
    (net (code "48") (name "WIFI_CLK_P") (class "Default")
      (node (ref "U6") (pin "47") (pinfunction "47_47") (pintype "unspecified"))
    )
    (net (code "49") (name "WIFI_RST_N") (class "Default")
      (node (ref "C35") (pin "2") (pinfunction "2_2") (pintype "unspecified"))
      (node (ref "R9") (pin "1") (pinfunction "1_1") (pintype "unspecified"))
      (node (ref "U6") (pin "52") (pinfunction "52_52") (pintype "unspecified"))
    )
    (net (code "50") (name "WIFI_RX_N") (class "Default")
      (node (ref "U6") (pin "37") (pinfunction "37_37") (pintype "unspecified"))
    )
    (net (code "51") (name "WIFI_RX_P") (class "Default")
      (node (ref "U6") (pin "35") (pinfunction "35_35") (pintype "unspecified"))
    )
    (net (code "52") (name "WIFI_TX_N") (class "Default")
      (node (ref "C34") (pin "2") (pinfunction "2_2") (pintype "unspecified"))
    )
    (net (code "53") (name "WIFI_TX_P") (class "Default")
      (node (ref "C33") (pin "2") (pinfunction "2_2") (pintype "unspecified"))
    )
    (net (code "54") (name "WIFI_WAKE_N") (class "Default")
      (node (ref "R13") (pin "2") (pinfunction "2_2") (pintype "unspecified"))
      (node (ref "U6") (pin "55") (pinfunction "55_55") (pintype "unspecified"))
    )
    (net (code "55") (name "unconnected-(CN1-P1-Pad8)") (class "Default")
      (node (ref "CN1") (pin "8") (pinfunction "P1_8") (pintype "unspecified+no_connect"))
    )
    (net (code "56") (name "unconnected-(CN1-P2-Pad9)") (class "Default")
      (node (ref "CN1") (pin "9") (pinfunction "P2_9") (pintype "unspecified+no_connect"))
    )
    (net (code "57") (name "unconnected-(CN1-P3-Pad10)") (class "Default")
      (node (ref "CN1") (pin "10") (pinfunction "P3_10") (pintype "unspecified+no_connect"))
    )
    (net (code "58") (name "unconnected-(CN1-P5-Pad22)") (class "Default")
      (node (ref "CN1") (pin "22") (pinfunction "P5_22") (pintype "unspecified+no_connect"))
    )
    (net (code "59") (name "unconnected-(CN1-P13-Pad20)") (class "Default")
      (node (ref "CN1") (pin "20") (pinfunction "P13_20") (pintype "unspecified+no_connect"))
    )
    (net (code "60") (name "unconnected-(CN1-P14-Pad21)") (class "Default")
      (node (ref "CN1") (pin "21") (pinfunction "P14_21") (pintype "unspecified+no_connect"))
    )
    (net (code "61") (name "unconnected-(CN2-P1-Pad8)") (class "Default")
      (node (ref "CN2") (pin "8") (pinfunction "P1_8") (pintype "unspecified+no_connect"))
    )
    (net (code "62") (name "unconnected-(CN2-P2-Pad9)") (class "Default")
      (node (ref "CN2") (pin "9") (pinfunction "P2_9") (pintype "unspecified+no_connect"))
    )
    (net (code "63") (name "unconnected-(CN2-P3-Pad10)") (class "Default")
      (node (ref "CN2") (pin "10") (pinfunction "P3_10") (pintype "unspecified+no_connect"))
    )
    (net (code "64") (name "unconnected-(CN2-P5-Pad22)") (class "Default")
      (node (ref "CN2") (pin "22") (pinfunction "P5_22") (pintype "unspecified+no_connect"))
    )
    (net (code "65") (name "unconnected-(CN2-P13-Pad20)") (class "Default")
      (node (ref "CN2") (pin "20") (pinfunction "P13_20") (pintype "unspecified+no_connect"))
    )
    (net (code "66") (name "unconnected-(CN2-P14-Pad21)") (class "Default")
      (node (ref "CN2") (pin "21") (pinfunction "P14_21") (pintype "unspecified+no_connect"))
    )
    (net (code "67") (name "unconnected-(R10-Pad1)") (class "Default")
      (node (ref "R10") (pin "1") (pinfunction "1_1") (pintype "unspecified"))
    )
    (net (code "68") (name "unconnected-(R10-Pad2)") (class "Default")
      (node (ref "R10") (pin "2") (pinfunction "2_2") (pintype "unspecified"))
    )
    (net (code "69") (name "unconnected-(U6-Pad6)") (class "Default")
      (node (ref "U6") (pin "6") (pinfunction "6_6") (pintype "unspecified"))
    )
    (net (code "70") (name "unconnected-(U6-Pad8)") (class "Default")
      (node (ref "U6") (pin "8") (pinfunction "8_8") (pintype "unspecified"))
    )
    (net (code "71") (name "unconnected-(U6-Pad9)") (class "Default")
      (node (ref "U6") (pin "9") (pinfunction "9_9") (pintype "unspecified"))
    )
    (net (code "72") (name "unconnected-(U6-Pad10)") (class "Default")
      (node (ref "U6") (pin "10") (pinfunction "10_10") (pintype "unspecified"))
    )
    (net (code "73") (name "unconnected-(U6-Pad11)") (class "Default")
      (node (ref "U6") (pin "11") (pinfunction "11_11") (pintype "unspecified"))
    )
    (net (code "74") (name "unconnected-(U6-Pad12)") (class "Default")
      (node (ref "U6") (pin "12") (pinfunction "12_12") (pintype "unspecified"))
    )
    (net (code "75") (name "unconnected-(U6-Pad13)") (class "Default")
      (node (ref "U6") (pin "13") (pinfunction "13_13") (pintype "unspecified"))
    )
    (net (code "76") (name "unconnected-(U6-Pad14)") (class "Default")
      (node (ref "U6") (pin "14") (pinfunction "14_14") (pintype "unspecified"))
    )
    (net (code "77") (name "unconnected-(U6-Pad15)") (class "Default")
      (node (ref "U6") (pin "15") (pinfunction "15_15") (pintype "unspecified"))
    )
    (net (code "78") (name "unconnected-(U6-Pad16)") (class "Default")
      (node (ref "U6") (pin "16") (pinfunction "16_16") (pintype "unspecified"))
    )
    (net (code "79") (name "unconnected-(U6-Pad17)") (class "Default")
      (node (ref "U6") (pin "17") (pinfunction "17_17") (pintype "unspecified"))
    )
    (net (code "80") (name "unconnected-(U6-Pad18)") (class "Default")
      (node (ref "U6") (pin "18") (pinfunction "18_18") (pintype "unspecified"))
    )
    (net (code "81") (name "unconnected-(U6-Pad19)") (class "Default")
      (node (ref "U6") (pin "19") (pinfunction "19_19") (pintype "unspecified"))
    )
    (net (code "82") (name "unconnected-(U6-Pad20)") (class "Default")
      (node (ref "U6") (pin "20") (pinfunction "20_20") (pintype "unspecified"))
    )
    (net (code "83") (name "unconnected-(U6-Pad21)") (class "Default")
      (node (ref "U6") (pin "21") (pinfunction "21_21") (pintype "unspecified"))
    )
    (net (code "84") (name "unconnected-(U6-Pad22)") (class "Default")
      (node (ref "U6") (pin "22") (pinfunction "22_22") (pintype "unspecified"))
    )
    (net (code "85") (name "unconnected-(U6-Pad23)") (class "Default")
      (node (ref "U6") (pin "23") (pinfunction "23_23") (pintype "unspecified"))
    )
    (net (code "86") (name "unconnected-(U6-Pad32)") (class "Default")
      (node (ref "U6") (pin "32") (pinfunction "32_32") (pintype "unspecified"))
    )
    (net (code "87") (name "unconnected-(U6-Pad34)") (class "Default")
      (node (ref "U6") (pin "34") (pinfunction "34_34") (pintype "unspecified"))
    )
    (net (code "88") (name "unconnected-(U6-Pad36)") (class "Default")
      (node (ref "U6") (pin "36") (pinfunction "36_36") (pintype "unspecified"))
    )
    (net (code "89") (name "unconnected-(U6-Pad38)") (class "Default")
      (node (ref "U6") (pin "38") (pinfunction "38_38") (pintype "unspecified"))
    )
    (net (code "90") (name "unconnected-(U6-Pad40)") (class "Default")
      (node (ref "U6") (pin "40") (pinfunction "40_40") (pintype "unspecified"))
    )
    (net (code "91") (name "unconnected-(U6-Pad42)") (class "Default")
      (node (ref "U6") (pin "42") (pinfunction "42_42") (pintype "unspecified"))
    )
    (net (code "92") (name "unconnected-(U6-Pad44)") (class "Default")
      (node (ref "U6") (pin "44") (pinfunction "44_44") (pintype "unspecified"))
    )
    (net (code "93") (name "unconnected-(U6-Pad46)") (class "Default")
      (node (ref "U6") (pin "46") (pinfunction "46_46") (pintype "unspecified"))
    )
    (net (code "94") (name "unconnected-(U6-Pad48)") (class "Default")
      (node (ref "U6") (pin "48") (pinfunction "48_48") (pintype "unspecified"))
    )
    (net (code "95") (name "unconnected-(U6-Pad50)") (class "Default")
      (node (ref "U6") (pin "50") (pinfunction "50_50") (pintype "unspecified"))
    )
    (net (code "96") (name "unconnected-(U6-Pad54)") (class "Default")
      (node (ref "U6") (pin "54") (pinfunction "54_54") (pintype "unspecified"))
    )
    (net (code "97") (name "unconnected-(U6-Pad56)") (class "Default")
      (node (ref "U6") (pin "56") (pinfunction "56_56") (pintype "unspecified"))
    )
    (net (code "98") (name "unconnected-(U6-Pad58)") (class "Default")
      (node (ref "U6") (pin "58") (pinfunction "58_58") (pintype "unspecified"))
    )
    (net (code "99") (name "unconnected-(U6-Pad59)") (class "Default")
      (node (ref "U6") (pin "59") (pinfunction "59_59") (pintype "unspecified"))
    )
    (net (code "100") (name "unconnected-(U6-Pad60)") (class "Default")
      (node (ref "U6") (pin "60") (pinfunction "60_60") (pintype "unspecified"))
    )
    (net (code "101") (name "unconnected-(U6-Pad61)") (class "Default")
      (node (ref "U6") (pin "61") (pinfunction "61_61") (pintype "unspecified"))
    )
    (net (code "102") (name "unconnected-(U6-Pad62)") (class "Default")
      (node (ref "U6") (pin "62") (pinfunction "62_62") (pintype "unspecified"))
    )
    (net (code "103") (name "unconnected-(U6-Pad64)") (class "Default")
      (node (ref "U6") (pin "64") (pinfunction "64_64") (pintype "unspecified"))
    )
    (net (code "104") (name "unconnected-(U6-Pad65)") (class "Default")
      (node (ref "U6") (pin "65") (pinfunction "65_65") (pintype "unspecified"))
    )
    (net (code "105") (name "unconnected-(U6-Pad66)") (class "Default")
      (node (ref "U6") (pin "66") (pinfunction "66_66") (pintype "unspecified"))
    )
    (net (code "106") (name "unconnected-(U6-Pad67)") (class "Default")
      (node (ref "U6") (pin "67") (pinfunction "67_67") (pintype "unspecified"))
    )
    (net (code "107") (name "unconnected-(U6-Pad68)") (class "Default")
      (node (ref "U6") (pin "68") (pinfunction "68_68") (pintype "unspecified"))
    )
    (net (code "108") (name "unconnected-(U6-Pad70)") (class "Default")
      (node (ref "U6") (pin "70") (pinfunction "70_70") (pintype "unspecified"))
    )
    (net (code "109") (name "unconnected-(U6-Pad71)") (class "Default")
      (node (ref "U6") (pin "71") (pinfunction "71_71") (pintype "unspecified"))
    )
    (net (code "110") (name "unconnected-(U6-Pad73)") (class "Default")
      (node (ref "U6") (pin "73") (pinfunction "73_73") (pintype "unspecified"))
    )
  )
)
